# weaver_led.net
KiCad netlist of a schematic drawn in EAGLE
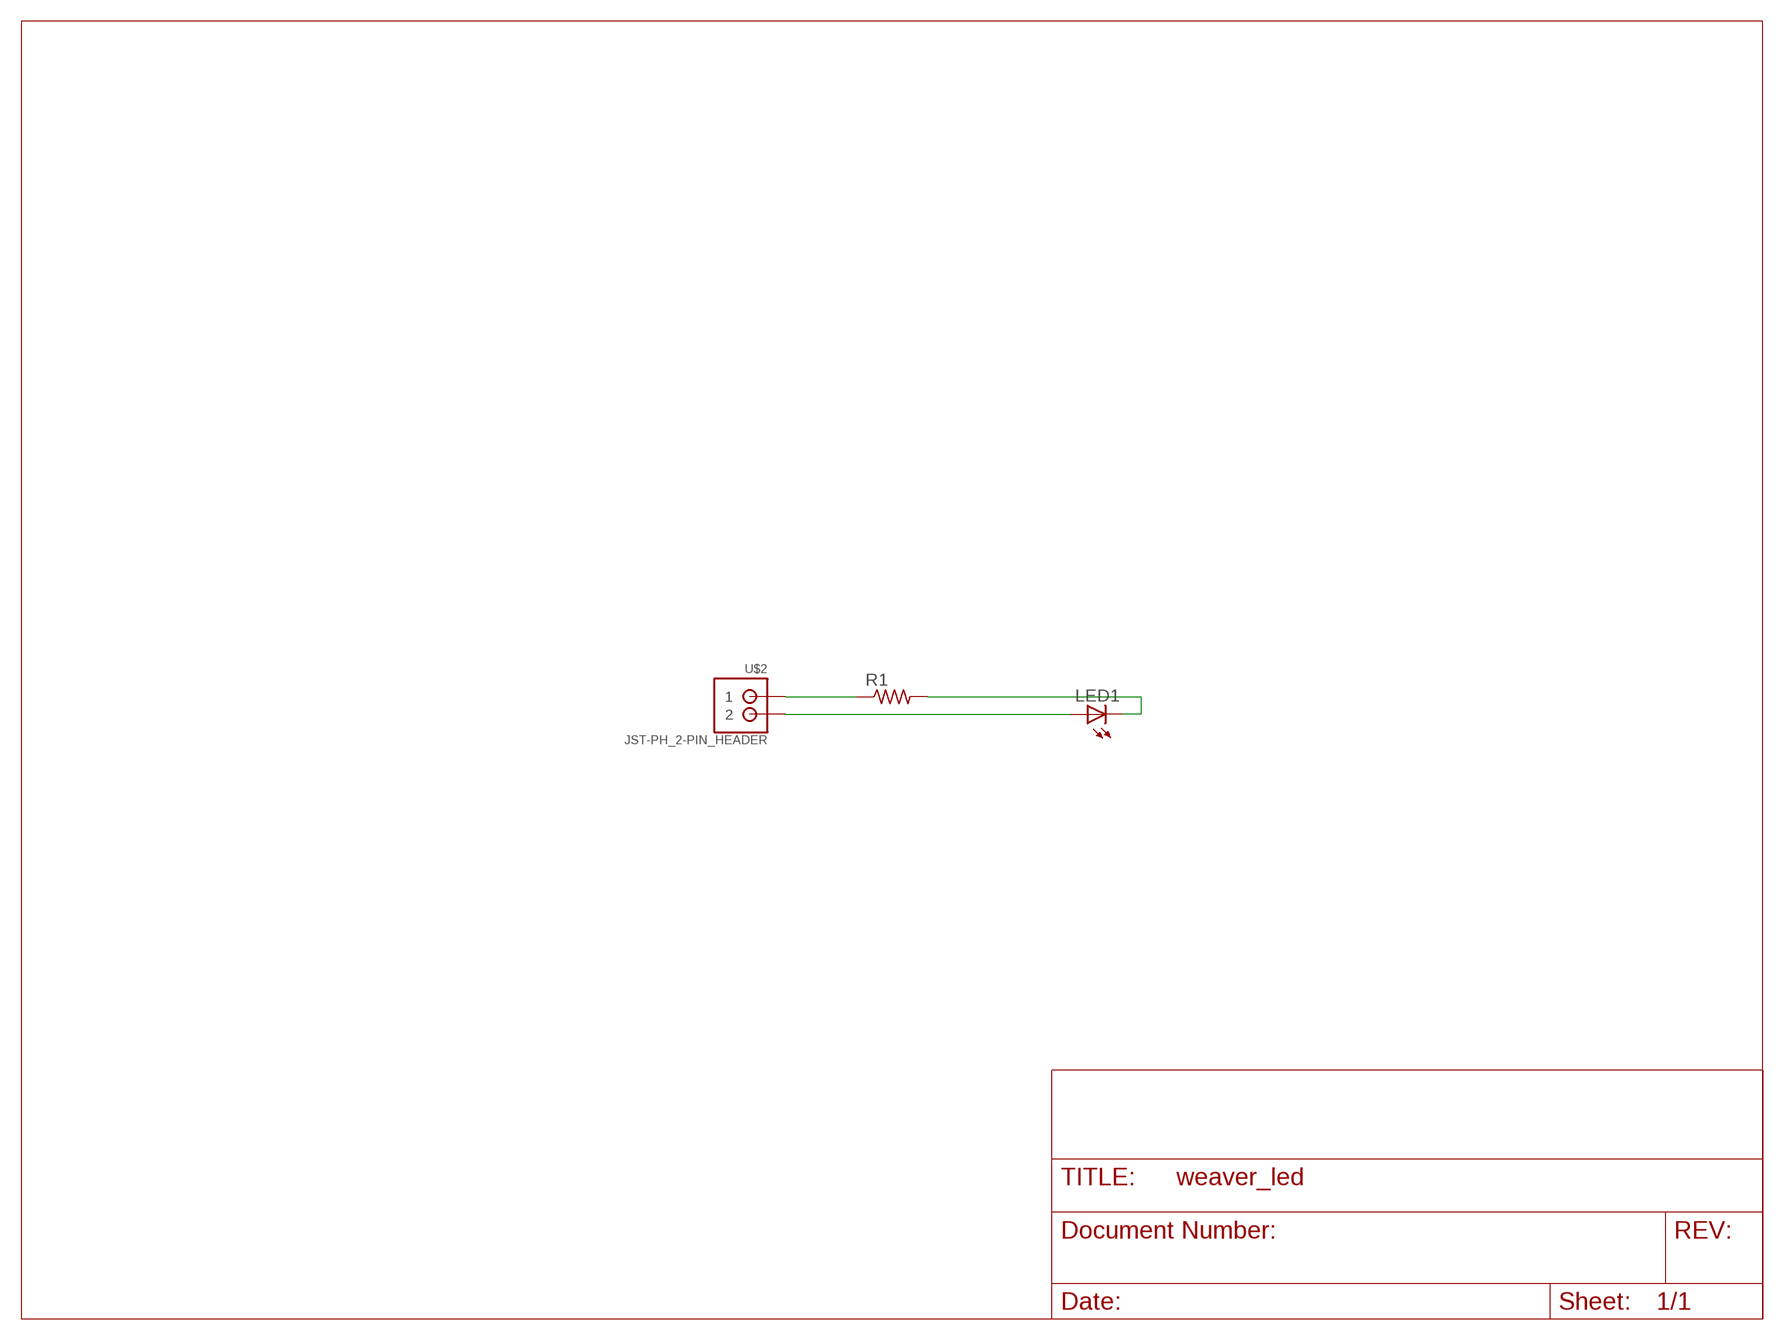
[diagram p0: schematic, sheet 1]

(export (version "E")
  (design (tool "Eeschema 10.0.6"))
  (components
    (comp (ref "LED1")
      (value "LED5MM")
      (footprint "eagle-import:LED5MM")
      (libsource (lib "eagle-import") (part "LED5MM"))
    )
    (comp (ref "R1")
      (value "R-US_R0805")
      (footprint "eagle-import:R0805")
      (libsource (lib "eagle-import") (part "R-US_R0805"))
    )
    (comp (ref "U$2")
      (value "JST-PH_2-PIN_HEADER")
      (footprint "eagle-import:JST_B2B-PH_HEADER")
      (libsource (lib "eagle-import") (part "JST-PH_2-PIN_HEADER"))
    )
  )
  (nets
    (net (code "1") (name "Net-(LED1-C)") (class "Default")
      (node (ref "LED1") (pin "K") (pinfunction "C_K") (pintype "passive"))
      (node (ref "R1") (pin "2") (pinfunction "2_2") (pintype "passive"))
    )
    (net (code "2") (name "Net-(U$2-1)") (class "Default")
      (node (ref "R1") (pin "1") (pinfunction "1_1") (pintype "passive"))
      (node (ref "U$2") (pin "P1") (pinfunction "1_P1") (pintype "bidirectional"))
    )
    (net (code "3") (name "Net-(U$2-2)") (class "Default")
      (node (ref "LED1") (pin "A") (pinfunction "A_A") (pintype "passive"))
      (node (ref "U$2") (pin "P2") (pinfunction "2_P2") (pintype "bidirectional"))
    )
  )
)
